# Review_PCD_1_5.net
KiCad netlist of a schematic drawn in EAGLE
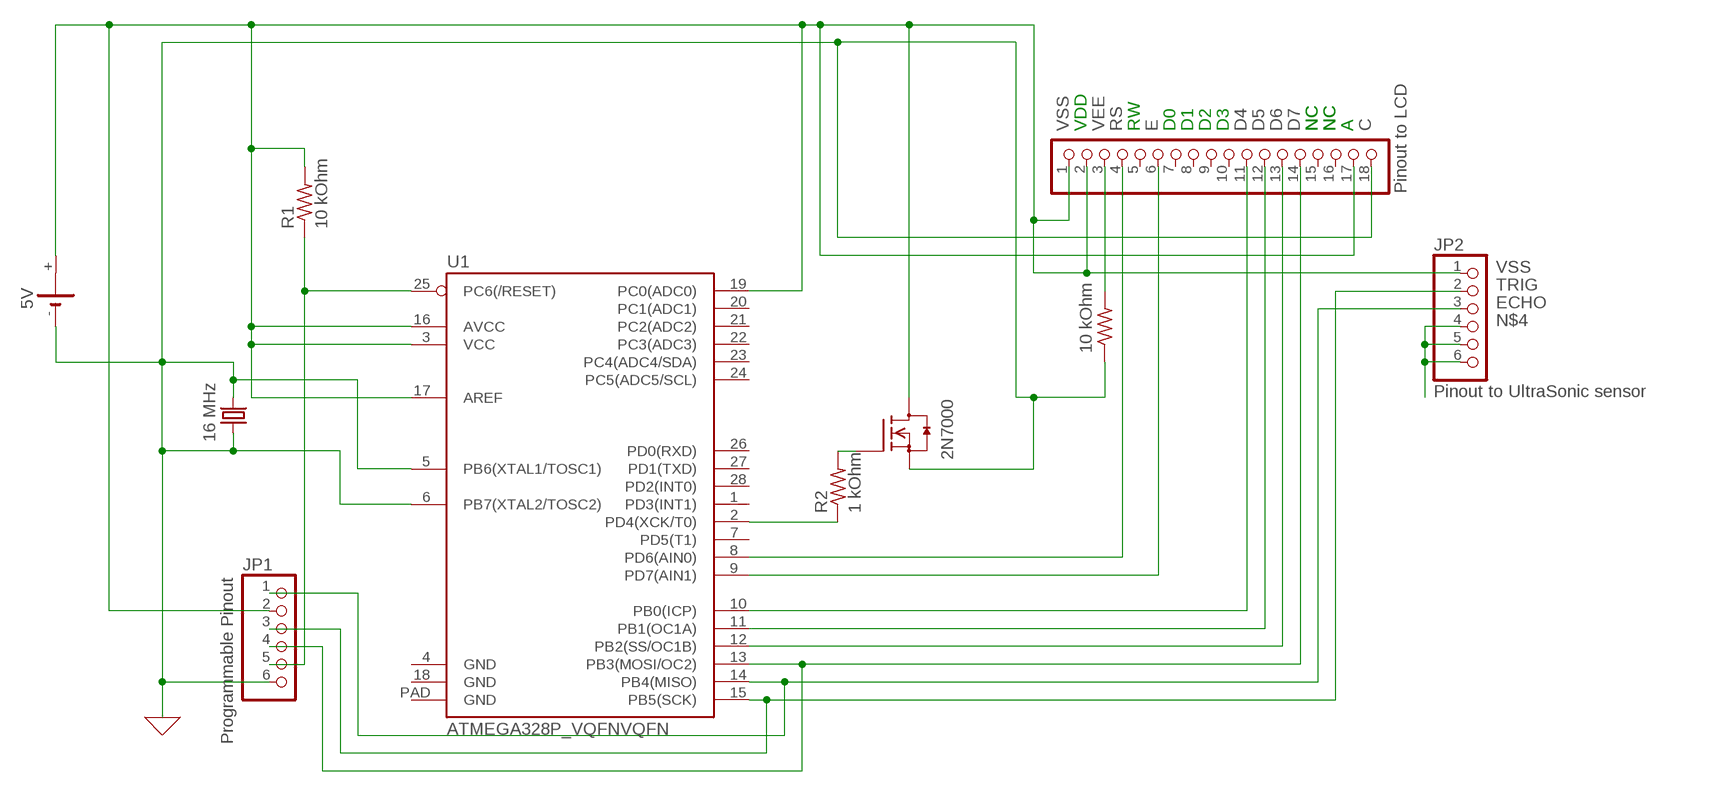
[diagram p0: schematic, sheet 1]

(export (version "E")
  (design (tool "Eeschema 10.0.6"))
  (components
    (comp (ref "5V")
      (value "CR1/2")
      (footprint "eagle-import:CR1_2")
      (libsource (lib "eagle-import") (part "CR1/2"))
    )
    (comp (ref "JP1")
      (value "Programmable Pinout")
      (footprint "eagle-import:1X06-3.5MM")
      (libsource (lib "eagle-import") (part "PINHD-1X6-3.5MM"))
    )
    (comp (ref "JP2")
      (value "Pinout to UltraSonic sensor")
      (footprint "eagle-import:1X06-BIG")
      (libsource (lib "eagle-import") (part "PINHD-1X6B"))
    )
    (comp (ref "JP3")
      (value "Pinout to LCD")
      (footprint "eagle-import:1X18")
      (libsource (lib "eagle-import") (part "PINHD-1X18"))
    )
    (comp (ref "Q1")
      (value "16 MHz")
      (footprint "eagle-import:1.6X1.2")
      (fields (field (name "Q1") "16 MHz"))
      (libsource (lib "eagle-import") (part "KX-4"))
    )
    (comp (ref "Q2")
      (value "2N7000")
      (footprint "eagle-import:TO92")
      (libsource (lib "eagle-import") (part "2N7000KL/BS170KL"))
    )
    (comp (ref "R1")
      (value "10 kOhm")
      (footprint "eagle-import:R2012W")
      (libsource (lib "eagle-import") (part "R-US_R2012W"))
    )
    (comp (ref "R2")
      (value "1 kOhm")
      (footprint "eagle-import:R2012W")
      (fields (field (name "R1") "1 kOhm"))
      (libsource (lib "eagle-import") (part "R-US_R2012W"))
    )
    (comp (ref "R3")
      (value "10 kOhm")
      (footprint "eagle-import:R2012W")
      (fields (field (name "R1") "10 kOhm"))
      (libsource (lib "eagle-import") (part "R-US_R2012W"))
    )
    (comp (ref "U1")
      (value "ATMEGA328P_VQFNVQFN")
      (footprint "eagle-import:VQFN-28")
      (libsource (lib "eagle-import") (part "ATMEGA328P_VQFNVQFN"))
    )
  )
  (nets
    (net (code "1") (name "/D4") (class "Default")
      (node (ref "JP3") (pin "11") (pinfunction "11_11") (pintype "passive"))
      (node (ref "U1") (pin "10") (pinfunction "PB0(ICP)_10") (pintype "bidirectional"))
    )
    (net (code "2") (name "/D5") (class "Default")
      (node (ref "JP3") (pin "12") (pinfunction "12_12") (pintype "passive"))
      (node (ref "U1") (pin "11") (pinfunction "PB1(OC1A)_11") (pintype "bidirectional"))
    )
    (net (code "3") (name "/D6") (class "Default")
      (node (ref "JP3") (pin "13") (pinfunction "13_13") (pintype "passive"))
      (node (ref "U1") (pin "12") (pinfunction "PB2(SS/OC1B)_12") (pintype "bidirectional"))
    )
    (net (code "4") (name "/D7") (class "Default")
      (node (ref "JP1") (pin "4") (pinfunction "4_4") (pintype "passive"))
      (node (ref "JP3") (pin "14") (pinfunction "14_14") (pintype "passive"))
      (node (ref "U1") (pin "13") (pinfunction "PB3(MOSI/OC2)_13") (pintype "bidirectional"))
    )
    (net (code "5") (name "/E") (class "Default")
      (node (ref "JP3") (pin "6") (pinfunction "6_6") (pintype "passive"))
      (node (ref "U1") (pin "9") (pinfunction "PD7(AIN1)_9") (pintype "bidirectional"))
    )
    (net (code "6") (name "/ECHO") (class "Default")
      (node (ref "JP1") (pin "1") (pinfunction "1_1") (pintype "passive"))
      (node (ref "JP2") (pin "3") (pinfunction "3_3") (pintype "passive"))
      (node (ref "U1") (pin "14") (pinfunction "PB4(MISO)_14") (pintype "bidirectional"))
    )
    (net (code "7") (name "/N$4") (class "Default")
      (node (ref "JP2") (pin "4") (pinfunction "4_4") (pintype "passive"))
      (node (ref "JP2") (pin "5") (pinfunction "5_5") (pintype "passive"))
      (node (ref "JP2") (pin "6") (pinfunction "6_6") (pintype "passive"))
    )
    (net (code "8") (name "/RS") (class "Default")
      (node (ref "JP3") (pin "4") (pinfunction "4_4") (pintype "passive"))
      (node (ref "U1") (pin "8") (pinfunction "PD6(AIN0)_8") (pintype "bidirectional"))
    )
    (net (code "9") (name "/TRIG") (class "Default")
      (node (ref "JP1") (pin "3") (pinfunction "3_3") (pintype "passive"))
      (node (ref "JP2") (pin "2") (pinfunction "2_2") (pintype "passive"))
      (node (ref "U1") (pin "15") (pinfunction "PB5(SCK)_15") (pintype "bidirectional"))
    )
    (net (code "10") (name "/VEE") (class "Default")
      (node (ref "JP3") (pin "3") (pinfunction "3_3") (pintype "passive"))
      (node (ref "R3") (pin "2") (pinfunction "2_2") (pintype "passive"))
    )
    (net (code "11") (name "/VSS") (class "Default")
      (node (ref "5V") (pin "+") (pinfunction "+_+") (pintype "passive"))
      (node (ref "JP1") (pin "2") (pinfunction "2_2") (pintype "passive"))
      (node (ref "JP2") (pin "1") (pinfunction "1_1") (pintype "passive"))
      (node (ref "JP3") (pin "1") (pinfunction "1_1") (pintype "passive"))
      (node (ref "JP3") (pin "17") (pinfunction "17_17") (pintype "passive"))
      (node (ref "JP3") (pin "2") (pinfunction "2_2") (pintype "passive"))
      (node (ref "Q2") (pin "3") (pinfunction "D_3") (pintype "passive"))
      (node (ref "R1") (pin "2") (pinfunction "2_2") (pintype "passive"))
      (node (ref "U1") (pin "16") (pinfunction "AVCC_16") (pintype "bidirectional"))
      (node (ref "U1") (pin "17") (pinfunction "AREF_17") (pintype "bidirectional"))
      (node (ref "U1") (pin "19") (pinfunction "PC0(ADC0)_19") (pintype "bidirectional"))
      (node (ref "U1") (pin "3") (pinfunction "VCC_3") (pintype "bidirectional"))
    )
    (net (code "12") (name "GND") (class "Default")
      (node (ref "5V") (pin "-") (pinfunction "-_-") (pintype "passive"))
      (node (ref "JP1") (pin "6") (pinfunction "6_6") (pintype "passive"))
      (node (ref "JP3") (pin "18") (pinfunction "18_18") (pintype "passive"))
      (node (ref "Q1") (pin "1") (pinfunction "1_1") (pintype "passive"))
      (node (ref "Q1") (pin "3") (pinfunction "2_3") (pintype "passive"))
      (node (ref "Q2") (pin "1") (pinfunction "S_1") (pintype "passive"))
      (node (ref "R3") (pin "1") (pinfunction "1_1") (pintype "passive"))
      (node (ref "U1") (pin "5") (pinfunction "PB6(XTAL1/TOSC1)_5") (pintype "bidirectional"))
      (node (ref "U1") (pin "6") (pinfunction "PB7(XTAL2/TOSC2)_6") (pintype "bidirectional"))
    )
    (net (code "13") (name "Net-(Q2-G)") (class "Default")
      (node (ref "Q2") (pin "2") (pinfunction "G_2") (pintype "passive"))
      (node (ref "R2") (pin "2") (pinfunction "2_2") (pintype "passive"))
    )
    (net (code "14") (name "Net-(U1-PC6({slash}RESET))") (class "Default")
      (node (ref "JP1") (pin "5") (pinfunction "5_5") (pintype "passive"))
      (node (ref "R1") (pin "1") (pinfunction "1_1") (pintype "passive"))
      (node (ref "U1") (pin "25") (pinfunction "PC6(/RESET)_25") (pintype "bidirectional"))
    )
    (net (code "15") (name "Net-(U1-PD4(XCK{slash}T0))") (class "Default")
      (node (ref "R2") (pin "1") (pinfunction "1_1") (pintype "passive"))
      (node (ref "U1") (pin "2") (pinfunction "PD4(XCK/T0)_2") (pintype "bidirectional"))
    )
    (net (code "16") (name "unconnected-(5V-+-Pad+@1)") (class "Default")
      (node (ref "5V") (pin "+@1") (pinfunction "+_+@1") (pintype "passive"))
    )
    (net (code "17") (name "unconnected-(JP3-Pad5)") (class "Default")
      (node (ref "JP3") (pin "5") (pinfunction "5_5") (pintype "passive"))
    )
    (net (code "18") (name "unconnected-(JP3-Pad7)") (class "Default")
      (node (ref "JP3") (pin "7") (pinfunction "7_7") (pintype "passive"))
    )
    (net (code "19") (name "unconnected-(JP3-Pad8)") (class "Default")
      (node (ref "JP3") (pin "8") (pinfunction "8_8") (pintype "passive"))
    )
    (net (code "20") (name "unconnected-(JP3-Pad9)") (class "Default")
      (node (ref "JP3") (pin "9") (pinfunction "9_9") (pintype "passive"))
    )
    (net (code "21") (name "unconnected-(JP3-Pad10)") (class "Default")
      (node (ref "JP3") (pin "10") (pinfunction "10_10") (pintype "passive"))
    )
    (net (code "22") (name "unconnected-(JP3-Pad15)") (class "Default")
      (node (ref "JP3") (pin "15") (pinfunction "15_15") (pintype "passive"))
    )
    (net (code "23") (name "unconnected-(JP3-Pad16)") (class "Default")
      (node (ref "JP3") (pin "16") (pinfunction "16_16") (pintype "passive"))
    )
    (net (code "24") (name "unconnected-(U1-GND-Pad4)") (class "Default")
      (node (ref "U1") (pin "4") (pinfunction "GND_4") (pintype "bidirectional"))
    )
    (net (code "25") (name "unconnected-(U1-GND-Pad18)") (class "Default")
      (node (ref "U1") (pin "18") (pinfunction "GND_18") (pintype "bidirectional"))
    )
    (net (code "26") (name "unconnected-(U1-GND-PadPAD)") (class "Default")
      (node (ref "U1") (pin "PAD") (pinfunction "GND_PAD") (pintype "bidirectional"))
    )
    (net (code "27") (name "unconnected-(U1-PC1(ADC1)-Pad20)") (class "Default")
      (node (ref "U1") (pin "20") (pinfunction "PC1(ADC1)_20") (pintype "bidirectional"))
    )
    (net (code "28") (name "unconnected-(U1-PC2(ADC2)-Pad21)") (class "Default")
      (node (ref "U1") (pin "21") (pinfunction "PC2(ADC2)_21") (pintype "bidirectional"))
    )
    (net (code "29") (name "unconnected-(U1-PC3(ADC3)-Pad22)") (class "Default")
      (node (ref "U1") (pin "22") (pinfunction "PC3(ADC3)_22") (pintype "bidirectional"))
    )
    (net (code "30") (name "unconnected-(U1-PC4(ADC4{slash}SDA)-Pad23)") (class "Default")
      (node (ref "U1") (pin "23") (pinfunction "PC4(ADC4/SDA)_23") (pintype "bidirectional"))
    )
    (net (code "31") (name "unconnected-(U1-PC5(ADC5{slash}SCL)-Pad24)") (class "Default")
      (node (ref "U1") (pin "24") (pinfunction "PC5(ADC5/SCL)_24") (pintype "bidirectional"))
    )
    (net (code "32") (name "unconnected-(U1-PD0(RXD)-Pad26)") (class "Default")
      (node (ref "U1") (pin "26") (pinfunction "PD0(RXD)_26") (pintype "bidirectional"))
    )
    (net (code "33") (name "unconnected-(U1-PD1(TXD)-Pad27)") (class "Default")
      (node (ref "U1") (pin "27") (pinfunction "PD1(TXD)_27") (pintype "bidirectional"))
    )
    (net (code "34") (name "unconnected-(U1-PD2(INT0)-Pad28)") (class "Default")
      (node (ref "U1") (pin "28") (pinfunction "PD2(INT0)_28") (pintype "bidirectional"))
    )
    (net (code "35") (name "unconnected-(U1-PD3(INT1)-Pad1)") (class "Default")
      (node (ref "U1") (pin "1") (pinfunction "PD3(INT1)_1") (pintype "bidirectional"))
    )
    (net (code "36") (name "unconnected-(U1-PD5(T1)-Pad7)") (class "Default")
      (node (ref "U1") (pin "7") (pinfunction "PD5(T1)_7") (pintype "bidirectional"))
    )
  )
)
